# design.net
KiCad netlist of a schematic drawn in Altium Designer
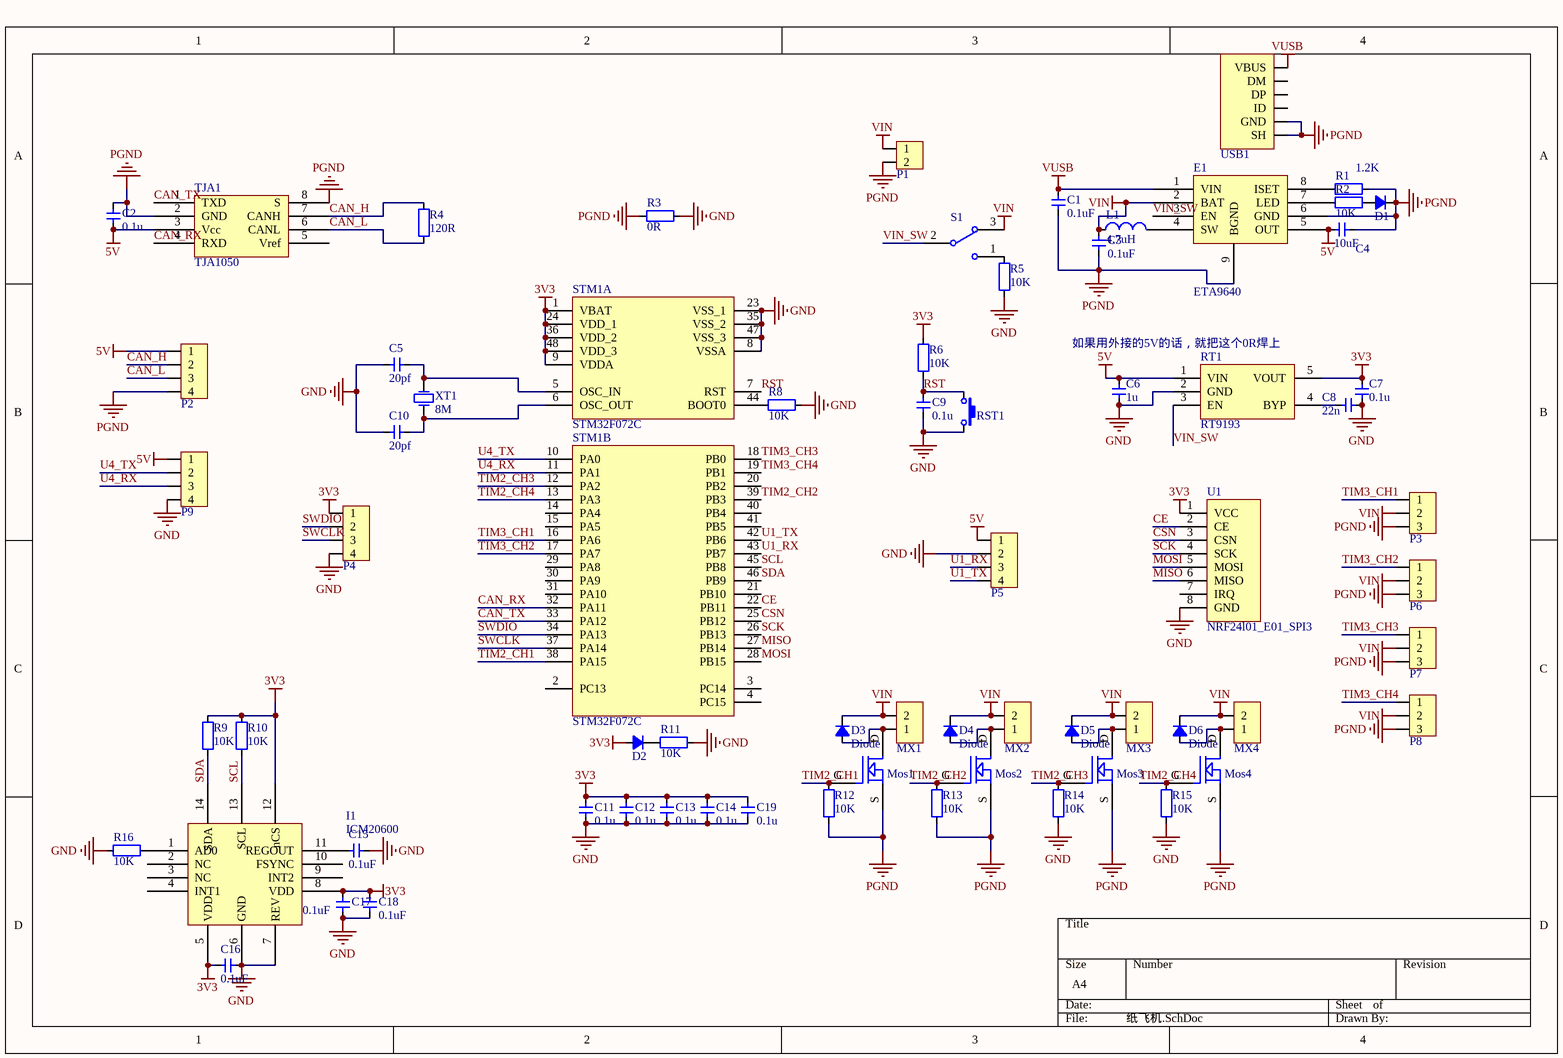
[diagram p0: 纸飞机.SchDoc]

(export (version "E")
  (design (tool "Eeschema 10.0.6"))
  (components
    (comp (ref "C1")
      (value "0.1uF")
      (footprint "PCB_PassiveCap:CAP_0603")
      (description "Capacitor")
      (fields (field (name "Comment") "Cap_0603"))
      (libsource (lib "SCH_Passive") (part "Cap_0603"))
    )
    (comp (ref "C2")
      (value "0.1u")
      (footprint "PCB_PassiveCap:CAP_0603")
      (description "Capacitor")
      (fields (field (name "Comment") "Cap_0603"))
      (libsource (lib "SCH_Passive") (part "Cap_0603"))
    )
    (comp (ref "C3")
      (value "0.1uF")
      (footprint "PCB_PassiveCap:CAP_0603")
      (description "Capacitor")
      (fields (field (name "Comment") "Cap_0603"))
      (libsource (lib "SCH_Passive") (part "Cap_0603"))
    )
    (comp (ref "C4")
      (value "10uF")
      (footprint "PCB_PassiveCap:CAP_0603")
      (description "Capacitor")
      (fields (field (name "Comment") "Cap_0603"))
      (libsource (lib "SCH_Passive") (part "Cap_0603"))
    )
    (comp (ref "C5")
      (value "20pf")
      (footprint "PCB_PassiveCap:CAP_0603")
      (description "Capacitor")
      (fields (field (name "Comment") "Cap_0603"))
      (libsource (lib "SCH_Passive") (part "Cap_0603"))
    )
    (comp (ref "C6")
      (value "1u")
      (footprint "PCB_PassiveCap:CAP_0603")
      (description "Capacitor")
      (fields (field (name "Comment") "Cap_0603"))
      (libsource (lib "SCH_Passive") (part "Cap_0603"))
    )
    (comp (ref "C7")
      (value "0.1u")
      (footprint "PCB_PassiveCap:CAP_0603")
      (description "Capacitor")
      (fields (field (name "Comment") "Cap_0603"))
      (libsource (lib "SCH_Passive") (part "Cap_0603"))
    )
    (comp (ref "C8")
      (value "22n")
      (footprint "PCB_PassiveCap:CAP_0603")
      (description "Capacitor")
      (fields (field (name "Comment") "Cap_0603"))
      (libsource (lib "SCH_Passive") (part "Cap_0603"))
    )
    (comp (ref "C9")
      (value "0.1u")
      (footprint "PCB_PassiveCap:CAP_0603")
      (description "Capacitor")
      (fields (field (name "Comment") "Cap_0603"))
      (libsource (lib "SCH_Passive") (part "Cap_0603"))
    )
    (comp (ref "C10")
      (value "20pf")
      (footprint "PCB_PassiveCap:CAP_0603")
      (description "Capacitor")
      (fields (field (name "Comment") "Cap_0603"))
      (libsource (lib "SCH_Passive") (part "Cap_0603"))
    )
    (comp (ref "C11")
      (value "0.1u")
      (footprint "PCB_PassiveCap:CAP_0603")
      (description "Capacitor")
      (fields (field (name "Comment") "Cap_0603"))
      (libsource (lib "SCH_Passive") (part "Cap_0603"))
    )
    (comp (ref "C12")
      (value "0.1u")
      (footprint "PCB_PassiveCap:CAP_0603")
      (description "Capacitor")
      (fields (field (name "Comment") "Cap_0603"))
      (libsource (lib "SCH_Passive") (part "Cap_0603"))
    )
    (comp (ref "C13")
      (value "0.1u")
      (footprint "PCB_PassiveCap:CAP_0603")
      (description "Capacitor")
      (fields (field (name "Comment") "Cap_0603"))
      (libsource (lib "SCH_Passive") (part "Cap_0603"))
    )
    (comp (ref "C14")
      (value "0.1u")
      (footprint "PCB_PassiveCap:CAP_0603")
      (description "Capacitor")
      (fields (field (name "Comment") "Cap_0603"))
      (libsource (lib "SCH_Passive") (part "Cap_0603"))
    )
    (comp (ref "C15")
      (value "0.1uF")
      (footprint "PCB_PassiveCap:CAP_0603")
      (description "Capacitor")
      (fields (field (name "Comment") "Cap_0603"))
      (libsource (lib "SCH_Passive") (part "Cap_0603"))
    )
    (comp (ref "C16")
      (value "0.1uF")
      (footprint "PCB_PassiveCap:CAP_0603")
      (description "Capacitor")
      (fields (field (name "Comment") "Cap_0603"))
      (libsource (lib "SCH_Passive") (part "Cap_0603"))
    )
    (comp (ref "C17")
      (value "0.1uF")
      (footprint "PCB_PassiveCap:CAP_0603")
      (description "Capacitor")
      (fields (field (name "Comment") "Cap_0603"))
      (libsource (lib "SCH_Passive") (part "Cap_0603"))
    )
    (comp (ref "C18")
      (value "0.1uF")
      (footprint "PCB_PassiveCap:CAP_0603")
      (description "Capacitor")
      (fields (field (name "Comment") "Cap_0603"))
      (libsource (lib "SCH_Passive") (part "Cap_0603"))
    )
    (comp (ref "C19")
      (value "0.1u")
      (footprint "PCB_PassiveCap:CAP_0603")
      (description "Capacitor")
      (fields (field (name "Comment") "Cap_0603"))
      (libsource (lib "SCH_Passive") (part "Cap_0603"))
    )
    (comp (ref "D1")
      (value "D_0805")
      (footprint "LED_0805_YELLOW")
      (libsource (lib "SCH_Active") (part "D_0805"))
    )
    (comp (ref "D2")
      (value "D_0805")
      (footprint "LED_0805_YELLOW")
      (libsource (lib "SCH_Active") (part "D_0805"))
    )
    (comp (ref "D3") (value "Diode") (footprint "LED_0805_RED") (libsource (lib "SCH_Active") (part "Diode")))
    (comp (ref "D4") (value "Diode") (footprint "LED_0805_RED") (libsource (lib "SCH_Active") (part "Diode")))
    (comp (ref "D5") (value "Diode") (footprint "LED_0805_RED") (libsource (lib "SCH_Active") (part "Diode")))
    (comp (ref "D6") (value "Diode") (footprint "LED_0805_RED") (libsource (lib "SCH_Active") (part "Diode")))
    (comp (ref "E1")
      (value "ETA9640")
      (footprint "SOP_E150_8 -with_PADs")
      (libsource (lib "SCH_IntegratedCircuit") (part "ETA9640"))
    )
    (comp (ref "I1")
      (value "ICM20600")
      (footprint "ICM20600")
      (libsource (lib "SCH_IntegratedCircuit") (part "ICM20600"))
    )
    (comp (ref "L1")
      (value "4.7uH")
      (footprint "PCB_PassiveInd:IND_CD32")
      (description "Inductor")
      (fields (field (name "Comment") "Ind_CD32"))
      (libsource (lib "SCH_Passive") (part "Ind_CD32"))
    )
    (comp (ref "Mos1")
      (value "MOSFET N")
      (footprint "Nmos_SOT23")
      (description "MOS SOT23")
      (libsource (lib "SCH_Active") (part "MOSFET N"))
    )
    (comp (ref "Mos2")
      (value "MOSFET N")
      (footprint "Nmos_SOT23")
      (description "MOS SOT23")
      (libsource (lib "SCH_Active") (part "MOSFET N"))
    )
    (comp (ref "Mos3")
      (value "MOSFET N")
      (footprint "Nmos_SOT23")
      (description "MOS SOT23")
      (libsource (lib "SCH_Active") (part "MOSFET N"))
    )
    (comp (ref "Mos4")
      (value "MOSFET N")
      (footprint "Nmos_SOT23")
      (description "MOS SOT23")
      (libsource (lib "SCH_Active") (part "MOSFET N"))
    )
    (comp (ref "MX1")
      (value "MX1.25_2P")
      (footprint "PCB_Connector:MX1.25_S90_2P")
      (description "MX")
      (libsource (lib "SCH_Connector") (part "MX1.25_2P"))
    )
    (comp (ref "MX2")
      (value "MX1.25_2P")
      (footprint "PCB_Connector:MX1.25_S90_2P")
      (description "MX")
      (libsource (lib "SCH_Connector") (part "MX1.25_2P"))
    )
    (comp (ref "MX3")
      (value "MX1.25_2P")
      (footprint "PCB_Connector:MX1.25_S90_2P")
      (description "MX")
      (libsource (lib "SCH_Connector") (part "MX1.25_2P"))
    )
    (comp (ref "MX4")
      (value "MX1.25_2P")
      (footprint "PCB_Connector:MX1.25_S90_2P")
      (description "MX")
      (libsource (lib "SCH_Connector") (part "MX1.25_2P"))
    )
    (comp (ref "P1")
      (value "HDR1x2_2.54")
      (footprint "PCB_ConnectorHDR:HDR1X2_2.54_180")
      (description "Header")
      (libsource (lib "SCH_ConnectorHDR") (part "HDR1x2_2.54"))
    )
    (comp (ref "P2")
      (value "HDR1x4_2.54")
      (footprint "1.25X4_SMT")
      (description "Header")
      (libsource (lib "SCH_ConnectorHDR") (part "HDR1x4_2.54"))
    )
    (comp (ref "P3")
      (value "HDR1x3_2.54")
      (footprint "1.25X3_SMT")
      (description "Header")
      (libsource (lib "SCH_ConnectorHDR") (part "HDR1x3_2.54"))
    )
    (comp (ref "P4")
      (value "HDR1x4_2.54")
      (footprint "PCB_ConnectorHDR:HDR1x4_2.54_180")
      (description "Header")
      (libsource (lib "SCH_ConnectorHDR") (part "HDR1x4_2.54"))
    )
    (comp (ref "P5")
      (value "HDR1x4_2.54")
      (footprint "PCB_ConnectorHDR:HDR1x4_2.54_180")
      (description "Header")
      (libsource (lib "SCH_ConnectorHDR") (part "HDR1x4_2.54"))
    )
    (comp (ref "P6")
      (value "HDR1x3_2.54")
      (footprint "1.25X3_SMT")
      (description "Header")
      (libsource (lib "SCH_ConnectorHDR") (part "HDR1x3_2.54"))
    )
    (comp (ref "P7")
      (value "HDR1x3_2.54")
      (footprint "1.25X3_SMT")
      (description "Header")
      (libsource (lib "SCH_ConnectorHDR") (part "HDR1x3_2.54"))
    )
    (comp (ref "P8")
      (value "HDR1x3_2.54")
      (footprint "1.25X3_SMT")
      (description "Header")
      (libsource (lib "SCH_ConnectorHDR") (part "HDR1x3_2.54"))
    )
    (comp (ref "P9")
      (value "HDR1x4_2.54")
      (footprint "1.25X4_SMT")
      (description "Header")
      (libsource (lib "SCH_ConnectorHDR") (part "HDR1x4_2.54"))
    )
    (comp (ref "R1")
      (value "1.2K")
      (footprint "PCB_PassiveRes:RES_0603")
      (description "Resistor")
      (fields (field (name "Comment") "Res_0603"))
      (libsource (lib "") (part "Res_0603_3"))
    )
    (comp (ref "R2")
      (value "10K")
      (footprint "PCB_PassiveRes:RES_0603")
      (description "Resistor")
      (fields (field (name "Comment") "Res_0603"))
      (libsource (lib "") (part "Res_0603_3"))
    )
    (comp (ref "R3")
      (value "0R")
      (footprint "PCB_PassiveRes:RES_0603")
      (description "Resistor")
      (fields (field (name "Comment") "Res_0603"))
      (libsource (lib "") (part "Res_0603_1"))
    )
    (comp (ref "R4")
      (value "120R")
      (footprint "PCB_PassiveRes:RES_0603")
      (description "Resistor")
      (fields (field (name "Comment") "Res_0603"))
      (libsource (lib "") (part "Res_0603_2"))
    )
    (comp (ref "R5")
      (value "10K")
      (footprint "PCB_PassiveRes:RES_0603")
      (description "Resistor")
      (fields (field (name "Comment") "Res_0603"))
      (libsource (lib "") (part "Res_0603_2"))
    )
    (comp (ref "R6")
      (value "10K")
      (footprint "PCB_PassiveRes:RES_0603")
      (description "Resistor")
      (fields (field (name "Comment") "Res_0603"))
      (libsource (lib "") (part "Res_0603_2"))
    )
    (comp (ref "R8")
      (value "10K")
      (footprint "PCB_PassiveRes:RES_0603")
      (description "Resistor")
      (fields (field (name "Comment") "Res_0603"))
      (libsource (lib "") (part "Res_0603_3"))
    )
    (comp (ref "R9")
      (value "10K")
      (footprint "PCB_PassiveRes:RES_0603")
      (description "Resistor")
      (fields (field (name "Comment") "Res_0603"))
      (libsource (lib "SCH_Passive") (part "Res_0603"))
    )
    (comp (ref "R10")
      (value "10K")
      (footprint "PCB_PassiveRes:RES_0603")
      (description "Resistor")
      (fields (field (name "Comment") "Res_0603"))
      (libsource (lib "SCH_Passive") (part "Res_0603"))
    )
    (comp (ref "R11")
      (value "10K")
      (footprint "PCB_PassiveRes:RES_0603")
      (description "Resistor")
      (fields (field (name "Comment") "Res_0603"))
      (libsource (lib "") (part "Res_0603_1"))
    )
    (comp (ref "R12")
      (value "10K")
      (footprint "PCB_PassiveRes:RES_0603")
      (description "Resistor")
      (fields (field (name "Comment") "Res_0603"))
      (libsource (lib "SCH_Passive") (part "Res_0603"))
    )
    (comp (ref "R13")
      (value "10K")
      (footprint "PCB_PassiveRes:RES_0603")
      (description "Resistor")
      (fields (field (name "Comment") "Res_0603"))
      (libsource (lib "SCH_Passive") (part "Res_0603"))
    )
    (comp (ref "R14")
      (value "10K")
      (footprint "PCB_PassiveRes:RES_0603")
      (description "Resistor")
      (fields (field (name "Comment") "Res_0603"))
      (libsource (lib "SCH_Passive") (part "Res_0603"))
    )
    (comp (ref "R15")
      (value "10K")
      (footprint "PCB_PassiveRes:RES_0603")
      (description "Resistor")
      (fields (field (name "Comment") "Res_0603"))
      (libsource (lib "SCH_Passive") (part "Res_0603"))
    )
    (comp (ref "R16")
      (value "10K")
      (footprint "PCB_PassiveRes:RES_0603")
      (description "Resistor")
      (fields (field (name "Comment") "Res_0603"))
      (libsource (lib "") (part "Res_0603_1"))
    )
    (comp (ref "RST1")
      (value "ButtonTACT_3x4x2_180")
      (footprint "PCB_Switch:ButtonTACT_3x4x2_180H")
      (description "Button")
      (libsource (lib "SCH_Switch") (part "ButtonTACT_3x4x2_180"))
    )
    (comp (ref "RT1")
      (value "RT9193")
      (footprint "PCB_IntegratedCircuit:SOT23-5")
      (description "Power")
      (libsource (lib "SCH_IntegratedCircuit") (part "RT9193"))
    )
    (comp (ref "S1")
      (value "SwitchSPDT_2.8x6.6_90")
      (footprint "PCB_Switch:SwitchSPDT_2.8X6.6_90")
      (description "Switch")
      (libsource (lib "SCH_Switch") (part "SwitchSPDT_2.8x6.6_90"))
    )
    (comp (ref "STM1")
      (value "STM32F072C")
      (footprint "PCB_IntegratedCircuit:LQFP_P0.5_48")
      (description "MCU")
      (libsource (lib "SCH_IntegratedCircuit") (part "STM32F103C"))
    )
    (comp (ref "TJA1")
      (value "TJA1050")
      (footprint "SOP_E150_8")
      (libsource (lib "SCH_IntegratedCircuit") (part "TJA1050"))
    )
    (comp (ref "U1")
      (value "NRF24l01_E01_SPI3")
      (footprint "E01-ML01SP2")
      (libsource (lib "SCH_Module") (part "NRF24l01_E01_SPI2"))
    )
    (comp (ref "USB1")
      (value "USB_Micro")
      (footprint "PCB_USB:USB_Micro-AB")
      (description "USB")
      (libsource (lib "SCH_USB") (part "USB_Micro"))
    )
    (comp (ref "XT1")
      (value "8M")
      (footprint "PCB_Oscillator:XT_5032_2")
      (description "Crystal Oscillator")
      (fields (field (name "Comment") "XTAL_5032_2P"))
      (libsource (lib "SCH_Oscillator") (part "XTAL_5032_2P"))
    )
  )
  (nets
    (net (code "1") (name "/CAN_H") (class "Default")
      (node (ref "P2") (pin "2") (pinfunction "2_2") (pintype "passive"))
      (node (ref "R4") (pin "2") (pinfunction "2_2") (pintype "passive"))
      (node (ref "TJA1") (pin "7") (pinfunction "CANH_7") (pintype "passive"))
    )
    (net (code "2") (name "/CAN_L") (class "Default")
      (node (ref "P2") (pin "3") (pinfunction "3_3") (pintype "passive"))
      (node (ref "R4") (pin "1") (pinfunction "1_1") (pintype "passive"))
      (node (ref "TJA1") (pin "6") (pinfunction "CANL_6") (pintype "passive"))
    )
    (net (code "3") (name "/CAN_RX") (class "Default")
      (node (ref "STM1") (pin "32") (pinfunction "PA11_32") (pintype "passive"))
      (node (ref "TJA1") (pin "4") (pinfunction "RXD_4") (pintype "passive"))
    )
    (net (code "4") (name "/CAN_TX") (class "Default")
      (node (ref "STM1") (pin "33") (pinfunction "PA12_33") (pintype "passive"))
      (node (ref "TJA1") (pin "1") (pinfunction "TXD_1") (pintype "passive"))
    )
    (net (code "5") (name "/CE") (class "Default")
      (node (ref "STM1") (pin "22") (pinfunction "PB11_22") (pintype "passive"))
      (node (ref "U1") (pin "2") (pinfunction "CE_2") (pintype "passive"))
    )
    (net (code "6") (name "/CSN") (class "Default")
      (node (ref "STM1") (pin "25") (pinfunction "PB12_25") (pintype "passive"))
      (node (ref "U1") (pin "3") (pinfunction "CSN_3") (pintype "passive"))
    )
    (net (code "7") (name "/MISO") (class "Default")
      (node (ref "STM1") (pin "27") (pinfunction "PB14_27") (pintype "passive"))
      (node (ref "U1") (pin "6") (pinfunction "MISO_6") (pintype "passive"))
    )
    (net (code "8") (name "/MOSI") (class "Default")
      (node (ref "STM1") (pin "28") (pinfunction "PB15_28") (pintype "passive"))
      (node (ref "U1") (pin "5") (pinfunction "MOSI_5") (pintype "passive"))
    )
    (net (code "9") (name "/RST") (class "Default")
      (node (ref "C9") (pin "2") (pinfunction "2_2") (pintype "passive"))
      (node (ref "R6") (pin "1") (pinfunction "1_1") (pintype "passive"))
      (node (ref "RST1") (pin "1") (pinfunction "1_1") (pintype "passive"))
      (node (ref "STM1") (pin "7") (pinfunction "RST_7") (pintype "passive"))
    )
    (net (code "10") (name "/SCK") (class "Default")
      (node (ref "STM1") (pin "26") (pinfunction "PB13_26") (pintype "passive"))
      (node (ref "U1") (pin "4") (pinfunction "SCK_4") (pintype "passive"))
    )
    (net (code "11") (name "/SCL") (class "Default")
      (node (ref "I1") (pin "13") (pinfunction "SCL_13") (pintype "passive"))
      (node (ref "R10") (pin "2") (pinfunction "2_2") (pintype "passive"))
      (node (ref "STM1") (pin "45") (pinfunction "PB8_45") (pintype "passive"))
    )
    (net (code "12") (name "/SDA") (class "Default")
      (node (ref "I1") (pin "14") (pinfunction "SDA_14") (pintype "passive"))
      (node (ref "R9") (pin "2") (pinfunction "2_2") (pintype "passive"))
      (node (ref "STM1") (pin "46") (pinfunction "PB9_46") (pintype "passive"))
    )
    (net (code "13") (name "/SWCLK") (class "Default")
      (node (ref "P4") (pin "3") (pinfunction "3_3") (pintype "passive"))
      (node (ref "STM1") (pin "37") (pinfunction "PA14_37") (pintype "passive"))
    )
    (net (code "14") (name "/SWDIO") (class "Default")
      (node (ref "P4") (pin "2") (pinfunction "2_2") (pintype "passive"))
      (node (ref "STM1") (pin "34") (pinfunction "PA13_34") (pintype "passive"))
    )
    (net (code "15") (name "/TIM2_CH1") (class "Default")
      (node (ref "Mos1") (pin "G") (pinfunction "G_G") (pintype "passive"))
      (node (ref "R12") (pin "1") (pinfunction "1_1") (pintype "passive"))
      (node (ref "STM1") (pin "38") (pinfunction "PA15_38") (pintype "passive"))
    )
    (net (code "16") (name "/TIM2_CH2") (class "Default")
      (node (ref "Mos2") (pin "G") (pinfunction "G_G") (pintype "passive"))
      (node (ref "R13") (pin "1") (pinfunction "1_1") (pintype "passive"))
      (node (ref "STM1") (pin "39") (pinfunction "PB3_39") (pintype "passive"))
    )
    (net (code "17") (name "/TIM2_CH3") (class "Default")
      (node (ref "Mos3") (pin "G") (pinfunction "G_G") (pintype "passive"))
      (node (ref "R14") (pin "1") (pinfunction "1_1") (pintype "passive"))
      (node (ref "STM1") (pin "12") (pinfunction "PA2_12") (pintype "passive"))
    )
    (net (code "18") (name "/TIM2_CH4") (class "Default")
      (node (ref "Mos4") (pin "G") (pinfunction "G_G") (pintype "passive"))
      (node (ref "R15") (pin "1") (pinfunction "1_1") (pintype "passive"))
      (node (ref "STM1") (pin "13") (pinfunction "PA3_13") (pintype "passive"))
    )
    (net (code "19") (name "/TIM3_CH1") (class "Default")
      (node (ref "P3") (pin "1") (pinfunction "1_1") (pintype "passive"))
      (node (ref "STM1") (pin "16") (pinfunction "PA6_16") (pintype "passive"))
    )
    (net (code "20") (name "/TIM3_CH2") (class "Default")
      (node (ref "P6") (pin "1") (pinfunction "1_1") (pintype "passive"))
      (node (ref "STM1") (pin "17") (pinfunction "PA7_17") (pintype "passive"))
    )
    (net (code "21") (name "/TIM3_CH3") (class "Default")
      (node (ref "P7") (pin "1") (pinfunction "1_1") (pintype "passive"))
      (node (ref "STM1") (pin "18") (pinfunction "PB0_18") (pintype "passive"))
    )
    (net (code "22") (name "/TIM3_CH4") (class "Default")
      (node (ref "P8") (pin "1") (pinfunction "1_1") (pintype "passive"))
      (node (ref "STM1") (pin "19") (pinfunction "PB1_19") (pintype "passive"))
    )
    (net (code "23") (name "/U1_RX") (class "Default")
      (node (ref "P5") (pin "3") (pinfunction "3_3") (pintype "passive"))
      (node (ref "STM1") (pin "43") (pinfunction "PB7_43") (pintype "passive"))
    )
    (net (code "24") (name "/U1_TX") (class "Default")
      (node (ref "P5") (pin "4") (pinfunction "4_4") (pintype "passive"))
      (node (ref "STM1") (pin "42") (pinfunction "PB6_42") (pintype "passive"))
    )
    (net (code "25") (name "/U4_RX") (class "Default")
      (node (ref "P9") (pin "3") (pinfunction "3_3") (pintype "passive"))
      (node (ref "STM1") (pin "11") (pinfunction "PA1_11") (pintype "passive"))
    )
    (net (code "26") (name "/U4_TX") (class "Default")
      (node (ref "P9") (pin "2") (pinfunction "2_2") (pintype "passive"))
      (node (ref "STM1") (pin "10") (pinfunction "PA0_10") (pintype "passive"))
    )
    (net (code "27") (name "/VIN_SW") (class "Default")
      (node (ref "E1") (pin "3") (pinfunction "EN_3") (pintype "passive"))
      (node (ref "RT1") (pin "3") (pinfunction "EN_3") (pintype "power_in"))
      (node (ref "S1") (pin "2") (pinfunction "2_2") (pintype "passive"))
    )
    (net (code "28") (name "3V3") (class "Default")
      (node (ref "C11") (pin "2") (pinfunction "2_2") (pintype "passive"))
      (node (ref "C12") (pin "2") (pinfunction "2_2") (pintype "passive"))
      (node (ref "C13") (pin "2") (pinfunction "2_2") (pintype "passive"))
      (node (ref "C14") (pin "2") (pinfunction "2_2") (pintype "passive"))
      (node (ref "C16") (pin "2") (pinfunction "2_2") (pintype "passive"))
      (node (ref "C17") (pin "1") (pinfunction "1_1") (pintype "passive"))
      (node (ref "C18") (pin "1") (pinfunction "1_1") (pintype "passive"))
      (node (ref "C19") (pin "2") (pinfunction "2_2") (pintype "passive"))
      (node (ref "C7") (pin "2") (pinfunction "2_2") (pintype "passive"))
      (node (ref "D2") (pin "1") (pinfunction "A_1") (pintype "passive"))
      (node (ref "I1") (pin "12") (pinfunction "nCS_12") (pintype "passive"))
      (node (ref "I1") (pin "5") (pinfunction "VDD_5") (pintype "passive"))
      (node (ref "I1") (pin "8") (pinfunction "VDD_8") (pintype "passive"))
      (node (ref "P4") (pin "1") (pinfunction "1_1") (pintype "passive"))
      (node (ref "R10") (pin "1") (pinfunction "1_1") (pintype "passive"))
      (node (ref "R6") (pin "2") (pinfunction "2_2") (pintype "passive"))
      (node (ref "R9") (pin "1") (pinfunction "1_1") (pintype "passive"))
      (node (ref "RT1") (pin "5") (pinfunction "VOUT_5") (pintype "passive"))
      (node (ref "STM1") (pin "1") (pinfunction "VBAT_1") (pintype "passive"))
      (node (ref "STM1") (pin "24") (pinfunction "VDD_1_24") (pintype "passive"))
      (node (ref "STM1") (pin "36") (pinfunction "VDD_2_36") (pintype "passive"))
      (node (ref "STM1") (pin "48") (pinfunction "VDD_3_48") (pintype "passive"))
      (node (ref "STM1") (pin "9") (pinfunction "VDDA_9") (pintype "passive"))
      (node (ref "U1") (pin "1") (pinfunction "VCC_1") (pintype "passive"))
    )
    (net (code "29") (name "5V") (class "Default")
      (node (ref "C2") (pin "1") (pinfunction "1_1") (pintype "passive"))
      (node (ref "C4") (pin "1") (pinfunction "1_1") (pintype "passive"))
      (node (ref "C6") (pin "2") (pinfunction "2_2") (pintype "passive"))
      (node (ref "E1") (pin "5") (pinfunction "OUT_5") (pintype "passive"))
      (node (ref "P2") (pin "1") (pinfunction "1_1") (pintype "passive"))
      (node (ref "P5") (pin "1") (pinfunction "1_1") (pintype "passive"))
      (node (ref "P9") (pin "1") (pinfunction "1_1") (pintype "passive"))
      (node (ref "RT1") (pin "1") (pinfunction "VIN_1") (pintype "passive"))
      (node (ref "TJA1") (pin "3") (pinfunction "Vcc_3") (pintype "passive"))
    )
    (net (code "30") (name "GND") (class "Default")
      (node (ref "C10") (pin "1") (pinfunction "1_1") (pintype "passive"))
      (node (ref "C11") (pin "1") (pinfunction "1_1") (pintype "passive"))
      (node (ref "C12") (pin "1") (pinfunction "1_1") (pintype "passive"))
      (node (ref "C13") (pin "1") (pinfunction "1_1") (pintype "passive"))
      (node (ref "C14") (pin "1") (pinfunction "1_1") (pintype "passive"))
      (node (ref "C15") (pin "2") (pinfunction "2_2") (pintype "passive"))
      (node (ref "C16") (pin "1") (pinfunction "1_1") (pintype "passive"))
      (node (ref "C17") (pin "2") (pinfunction "2_2") (pintype "passive"))
      (node (ref "C18") (pin "2") (pinfunction "2_2") (pintype "passive"))
      (node (ref "C19") (pin "1") (pinfunction "1_1") (pintype "passive"))
      (node (ref "C5") (pin "1") (pinfunction "1_1") (pintype "passive"))
      (node (ref "C6") (pin "1") (pinfunction "1_1") (pintype "passive"))
      (node (ref "C7") (pin "1") (pinfunction "1_1") (pintype "passive"))
      (node (ref "C8") (pin "1") (pinfunction "1_1") (pintype "passive"))
      (node (ref "C9") (pin "1") (pinfunction "1_1") (pintype "passive"))
      (node (ref "I1") (pin "6") (pinfunction "GND_6") (pintype "passive"))
      (node (ref "I1") (pin "7") (pinfunction "REV_7") (pintype "passive"))
      (node (ref "P4") (pin "4") (pinfunction "4_4") (pintype "passive"))
      (node (ref "P5") (pin "2") (pinfunction "2_2") (pintype "passive"))
      (node (ref "P9") (pin "4") (pinfunction "4_4") (pintype "passive"))
      (node (ref "R11") (pin "2") (pinfunction "2_2") (pintype "passive"))
      (node (ref "R14") (pin "2") (pinfunction "2_2") (pintype "passive"))
      (node (ref "R15") (pin "2") (pinfunction "2_2") (pintype "passive"))
      (node (ref "R16") (pin "1") (pinfunction "1_1") (pintype "passive"))
      (node (ref "R3") (pin "2") (pinfunction "2_2") (pintype "passive"))
      (node (ref "R5") (pin "1") (pinfunction "1_1") (pintype "passive"))
      (node (ref "R8") (pin "1") (pinfunction "1_1") (pintype "passive"))
      (node (ref "RST1") (pin "2") (pinfunction "2_2") (pintype "passive"))
      (node (ref "RT1") (pin "2") (pinfunction "GND_2") (pintype "passive"))
      (node (ref "STM1") (pin "23") (pinfunction "VSS_1_23") (pintype "passive"))
      (node (ref "STM1") (pin "35") (pinfunction "VSS_2_35") (pintype "passive"))
      (node (ref "STM1") (pin "47") (pinfunction "VSS_3_47") (pintype "passive"))
      (node (ref "STM1") (pin "8") (pinfunction "VSSA_8") (pintype "passive"))
      (node (ref "U1") (pin "8") (pinfunction "GND_8") (pintype "passive"))
    )
    (net (code "31") (name "Net-(D1-A)") (class "Default")
      (node (ref "D1") (pin "1") (pinfunction "A_1") (pintype "passive"))
      (node (ref "R2") (pin "1") (pinfunction "1_1") (pintype "passive"))
    )
    (net (code "32") (name "Net-(D2-K)") (class "Default")
      (node (ref "D2") (pin "2") (pinfunction "K_2") (pintype "passive"))
      (node (ref "R11") (pin "1") (pinfunction "1_1") (pintype "passive"))
    )
    (net (code "33") (name "Net-(D3-A)") (class "Default")
      (node (ref "D3") (pin "1") (pinfunction "A_1") (pintype "passive"))
      (node (ref "MX1") (pin "1") (pinfunction "1_1") (pintype "passive"))
      (node (ref "Mos1") (pin "D") (pinfunction "D_D") (pintype "passive"))
    )
    (net (code "34") (name "Net-(D4-A)") (class "Default")
      (node (ref "D4") (pin "1") (pinfunction "A_1") (pintype "passive"))
      (node (ref "MX2") (pin "1") (pinfunction "1_1") (pintype "passive"))
      (node (ref "Mos2") (pin "D") (pinfunction "D_D") (pintype "passive"))
    )
    (net (code "35") (name "Net-(D5-A)") (class "Default")
      (node (ref "D5") (pin "1") (pinfunction "A_1") (pintype "passive"))
      (node (ref "MX3") (pin "1") (pinfunction "1_1") (pintype "passive"))
      (node (ref "Mos3") (pin "D") (pinfunction "D_D") (pintype "passive"))
    )
    (net (code "36") (name "Net-(D6-A)") (class "Default")
      (node (ref "D6") (pin "1") (pinfunction "A_1") (pintype "passive"))
      (node (ref "MX4") (pin "1") (pinfunction "1_1") (pintype "passive"))
      (node (ref "Mos4") (pin "D") (pinfunction "D_D") (pintype "passive"))
    )
    (net (code "37") (name "Net-(E1-ISET)") (class "Default")
      (node (ref "E1") (pin "8") (pinfunction "ISET_8") (pintype "passive"))
      (node (ref "R1") (pin "2") (pinfunction "2_2") (pintype "passive"))
    )
    (net (code "38") (name "Net-(E1-LED)") (class "Default")
      (node (ref "E1") (pin "7") (pinfunction "LED_7") (pintype "passive"))
      (node (ref "R2") (pin "2") (pinfunction "2_2") (pintype "passive"))
    )
    (net (code "39") (name "Net-(E1-SW)") (class "Default")
      (node (ref "E1") (pin "4") (pinfunction "SW_4") (pintype "passive"))
      (node (ref "L1") (pin "2") (pinfunction "2_2") (pintype "passive"))
    )
    (net (code "40") (name "Net-(I1-AD0)") (class "Default")
      (node (ref "I1") (pin "1") (pinfunction "AD0_1") (pintype "passive"))
      (node (ref "R16") (pin "2") (pinfunction "2_2") (pintype "passive"))
    )
    (net (code "41") (name "Net-(I1-REGOUT)") (class "Default")
      (node (ref "C15") (pin "1") (pinfunction "1_1") (pintype "passive"))
      (node (ref "I1") (pin "11") (pinfunction "REGOUT_11") (pintype "passive"))
    )
    (net (code "42") (name "Net-(R5-Pad2)") (class "Default")
      (node (ref "R5") (pin "2") (pinfunction "2_2") (pintype "passive"))
      (node (ref "S1") (pin "1") (pinfunction "1_1") (pintype "passive"))
    )
    (net (code "43") (name "Net-(RT1-BYP)") (class "Default")
      (node (ref "C8") (pin "2") (pinfunction "2_2") (pintype "passive"))
      (node (ref "RT1") (pin "4") (pinfunction "BYP_4") (pintype "passive"))
    )
    (net (code "44") (name "Net-(STM1A-BOOT0)") (class "Default")
      (node (ref "R8") (pin "2") (pinfunction "2_2") (pintype "passive"))
      (node (ref "STM1") (pin "44") (pinfunction "BOOT0_44") (pintype "passive"))
    )
    (net (code "45") (name "Net-(STM1A-OSC_IN)") (class "Default")
      (node (ref "C5") (pin "2") (pinfunction "2_2") (pintype "passive"))
      (node (ref "STM1") (pin "5") (pinfunction "OSC_IN_5") (pintype "passive"))
      (node (ref "XT1") (pin "2") (pinfunction "OSC2_2") (pintype "passive"))
    )
    (net (code "46") (name "Net-(STM1A-OSC_OUT)") (class "Default")
      (node (ref "C10") (pin "2") (pinfunction "2_2") (pintype "passive"))
      (node (ref "STM1") (pin "6") (pinfunction "OSC_OUT_6") (pintype "passive"))
      (node (ref "XT1") (pin "1") (pinfunction "OSC1_1") (pintype "passive"))
    )
    (net (code "47") (name "PGND") (class "Default")
      (node (ref "C1") (pin "2") (pinfunction "2_2") (pintype "passive"))
      (node (ref "C2") (pin "2") (pinfunction "2_2") (pintype "passive"))
      (node (ref "C3") (pin "2") (pinfunction "2_2") (pintype "passive"))
      (node (ref "C4") (pin "2") (pinfunction "2_2") (pintype "passive"))
      (node (ref "D1") (pin "2") (pinfunction "K_2") (pintype "passive"))
      (node (ref "E1") (pin "6") (pinfunction "GND_6") (pintype "passive"))
      (node (ref "E1") (pin "9") (pinfunction "BGND_9") (pintype "passive"))
      (node (ref "Mos1") (pin "S") (pinfunction "S_S") (pintype "passive"))
      (node (ref "Mos2") (pin "S") (pinfunction "S_S") (pintype "passive"))
      (node (ref "Mos3") (pin "S") (pinfunction "S_S") (pintype "passive"))
      (node (ref "Mos4") (pin "S") (pinfunction "S_S") (pintype "passive"))
      (node (ref "P1") (pin "2") (pinfunction "2_2") (pintype "passive"))
      (node (ref "P2") (pin "4") (pinfunction "4_4") (pintype "passive"))
      (node (ref "P3") (pin "3") (pinfunction "3_3") (pintype "passive"))
      (node (ref "P6") (pin "3") (pinfunction "3_3") (pintype "passive"))
      (node (ref "P7") (pin "3") (pinfunction "3_3") (pintype "passive"))
      (node (ref "P8") (pin "3") (pinfunction "3_3") (pintype "passive"))
      (node (ref "R1") (pin "1") (pinfunction "1_1") (pintype "passive"))
      (node (ref "R12") (pin "2") (pinfunction "2_2") (pintype "passive"))
      (node (ref "R13") (pin "2") (pinfunction "2_2") (pintype "passive"))
      (node (ref "R3") (pin "1") (pinfunction "1_1") (pintype "passive"))
      (node (ref "TJA1") (pin "2") (pinfunction "GND_2") (pintype "passive"))
      (node (ref "TJA1") (pin "8") (pinfunction "S_8") (pintype "passive"))
      (node (ref "USB1") (pin "0") (pinfunction "SH_0") (pintype "passive"))
      (node (ref "USB1") (pin "5") (pinfunction "GND_5") (pintype "passive"))
    )
    (net (code "48") (name "VIN") (class "Default")
      (node (ref "C3") (pin "1") (pinfunction "1_1") (pintype "passive"))
      (node (ref "D3") (pin "2") (pinfunction "K_2") (pintype "passive"))
      (node (ref "D4") (pin "2") (pinfunction "K_2") (pintype "passive"))
      (node (ref "D5") (pin "2") (pinfunction "K_2") (pintype "passive"))
      (node (ref "D6") (pin "2") (pinfunction "K_2") (pintype "passive"))
      (node (ref "E1") (pin "2") (pinfunction "BAT_2") (pintype "passive"))
      (node (ref "L1") (pin "1") (pinfunction "1_1") (pintype "passive"))
      (node (ref "MX1") (pin "2") (pinfunction "2_2") (pintype "passive"))
      (node (ref "MX2") (pin "2") (pinfunction "2_2") (pintype "passive"))
      (node (ref "MX3") (pin "2") (pinfunction "2_2") (pintype "passive"))
      (node (ref "MX4") (pin "2") (pinfunction "2_2") (pintype "passive"))
      (node (ref "P1") (pin "1") (pinfunction "1_1") (pintype "passive"))
      (node (ref "P3") (pin "2") (pinfunction "2_2") (pintype "passive"))
      (node (ref "P6") (pin "2") (pinfunction "2_2") (pintype "passive"))
      (node (ref "P7") (pin "2") (pinfunction "2_2") (pintype "passive"))
      (node (ref "P8") (pin "2") (pinfunction "2_2") (pintype "passive"))
      (node (ref "S1") (pin "3") (pinfunction "3_3") (pintype "passive"))
    )
    (net (code "49") (name "VUSB") (class "Default")
      (node (ref "C1") (pin "1") (pinfunction "1_1") (pintype "passive"))
      (node (ref "E1") (pin "1") (pinfunction "VIN_1") (pintype "passive"))
      (node (ref "USB1") (pin "1") (pinfunction "VBUS_1") (pintype "passive"))
    )
    (net (code "50") (name "unconnected-(I1-FSYNC-Pad10)") (class "Default")
      (node (ref "I1") (pin "10") (pinfunction "FSYNC_10") (pintype "passive"))
    )
    (net (code "51") (name "unconnected-(I1-INT1-Pad4)") (class "Default")
      (node (ref "I1") (pin "4") (pinfunction "INT1_4") (pintype "passive"))
    )
    (net (code "52") (name "unconnected-(I1-INT2-Pad9)") (class "Default")
      (node (ref "I1") (pin "9") (pinfunction "INT2_9") (pintype "passive"))
    )
    (net (code "53") (name "unconnected-(I1-NC-Pad2)") (class "Default")
      (node (ref "I1") (pin "2") (pinfunction "NC_2") (pintype "passive"))
    )
    (net (code "54") (name "unconnected-(I1-NC-Pad3)") (class "Default")
      (node (ref "I1") (pin "3") (pinfunction "NC_3") (pintype "passive"))
    )
    (net (code "55") (name "unconnected-(STM1B-PA4-Pad14)") (class "Default")
      (node (ref "STM1") (pin "14") (pinfunction "PA4_14") (pintype "passive"))
    )
    (net (code "56") (name "unconnected-(STM1B-PA5-Pad15)") (class "Default")
      (node (ref "STM1") (pin "15") (pinfunction "PA5_15") (pintype "passive"))
    )
    (net (code "57") (name "unconnected-(STM1B-PA8-Pad29)") (class "Default")
      (node (ref "STM1") (pin "29") (pinfunction "PA8_29") (pintype "passive"))
    )
    (net (code "58") (name "unconnected-(STM1B-PA9-Pad30)") (class "Default")
      (node (ref "STM1") (pin "30") (pinfunction "PA9_30") (pintype "passive"))
    )
    (net (code "59") (name "unconnected-(STM1B-PA10-Pad31)") (class "Default")
      (node (ref "STM1") (pin "31") (pinfunction "PA10_31") (pintype "passive"))
    )
    (net (code "60") (name "unconnected-(STM1B-PB2-Pad20)") (class "Default")
      (node (ref "STM1") (pin "20") (pinfunction "PB2_20") (pintype "passive"))
    )
    (net (code "61") (name "unconnected-(STM1B-PB4-Pad40)") (class "Default")
      (node (ref "STM1") (pin "40") (pinfunction "PB4_40") (pintype "passive"))
    )
    (net (code "62") (name "unconnected-(STM1B-PB5-Pad41)") (class "Default")
      (node (ref "STM1") (pin "41") (pinfunction "PB5_41") (pintype "passive"))
    )
    (net (code "63") (name "unconnected-(STM1B-PB10-Pad21)") (class "Default")
      (node (ref "STM1") (pin "21") (pinfunction "PB10_21") (pintype "passive"))
    )
    (net (code "64") (name "unconnected-(STM1B-PC13-Pad2)") (class "Default")
      (node (ref "STM1") (pin "2") (pinfunction "PC13_2") (pintype "passive"))
    )
    (net (code "65") (name "unconnected-(STM1B-PC14-Pad3)") (class "Default")
      (node (ref "STM1") (pin "3") (pinfunction "PC14_3") (pintype "passive"))
    )
    (net (code "66") (name "unconnected-(STM1B-PC15-Pad4)") (class "Default")
      (node (ref "STM1") (pin "4") (pinfunction "PC15_4") (pintype "passive"))
    )
    (net (code "67") (name "unconnected-(TJA1-Vref-Pad5)") (class "Default")
      (node (ref "TJA1") (pin "5") (pinfunction "Vref_5") (pintype "passive"))
    )
    (net (code "68") (name "unconnected-(U1-IRQ-Pad7)") (class "Default")
      (node (ref "U1") (pin "7") (pinfunction "IRQ_7") (pintype "passive"))
    )
    (net (code "69") (name "unconnected-(USB1-DM-Pad2)") (class "Default")
      (node (ref "USB1") (pin "2") (pinfunction "DM_2") (pintype "passive"))
    )
    (net (code "70") (name "unconnected-(USB1-DP-Pad3)") (class "Default")
      (node (ref "USB1") (pin "3") (pinfunction "DP_3") (pintype "passive"))
    )
    (net (code "71") (name "unconnected-(USB1-ID-Pad4)") (class "Default")
      (node (ref "USB1") (pin "4") (pinfunction "ID_4") (pintype "passive"))
    )
  )
)
